# Rev05MergeRedux--LevelShifting_Isolation.net
KiCad netlist of a schematic drawn in Altium Designer
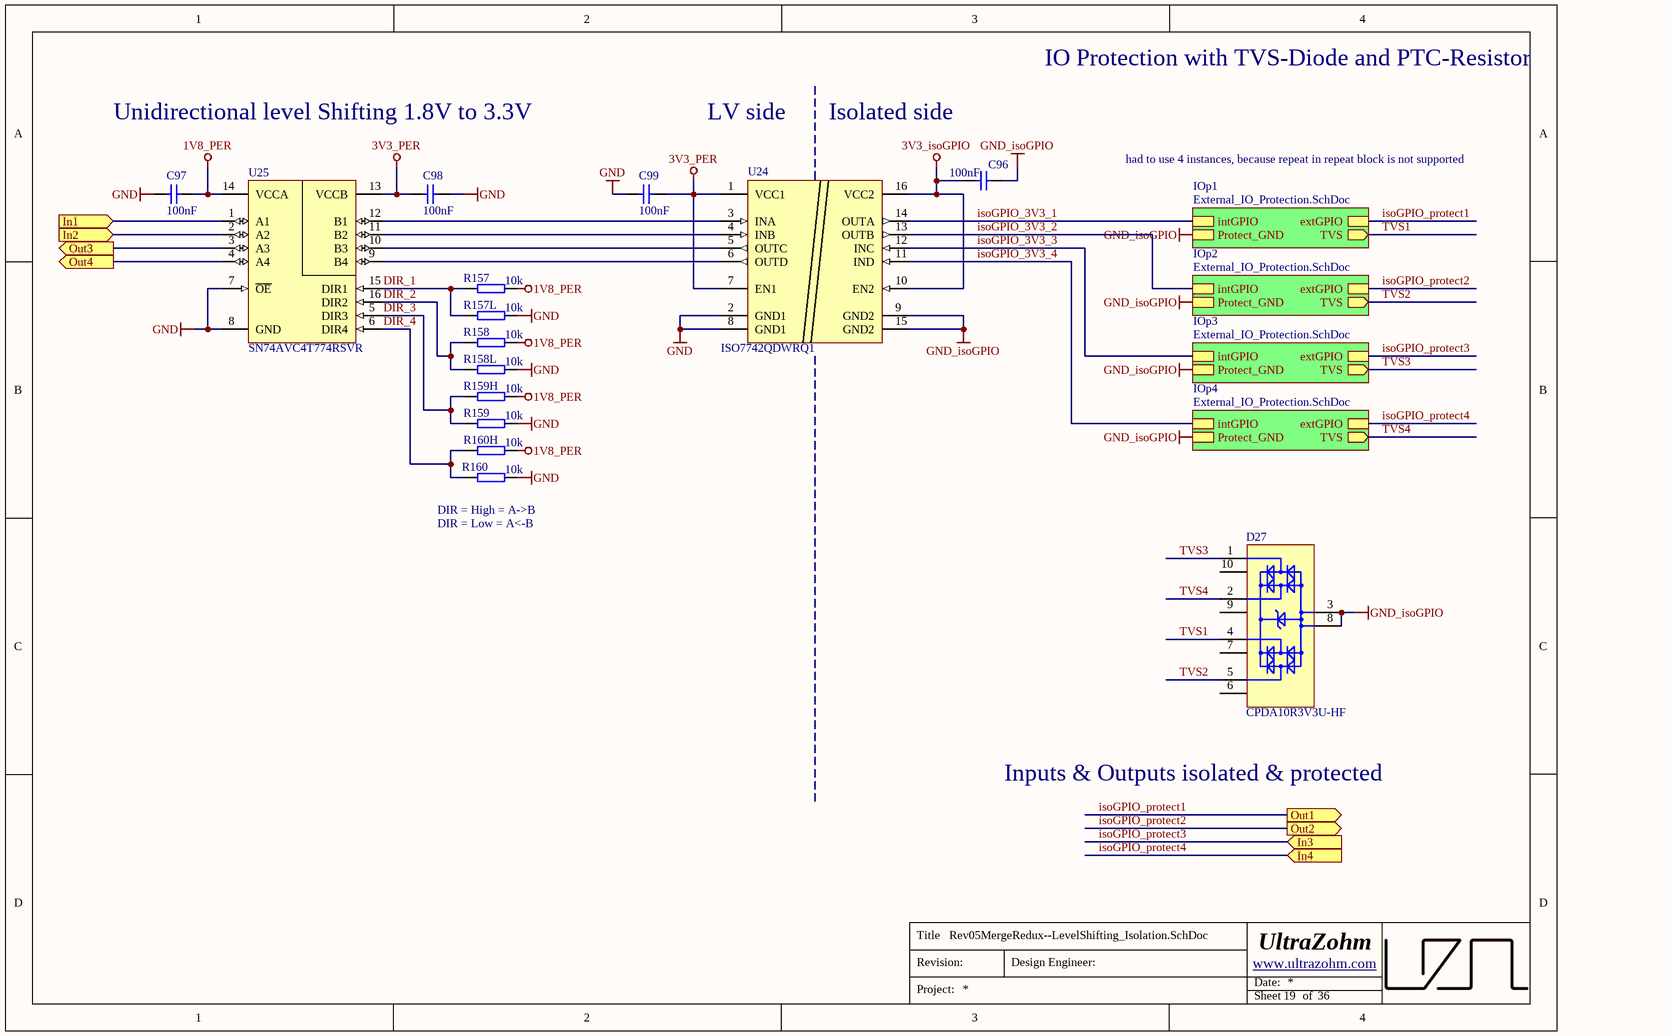
[diagram p0: Rev05MergeRedux--LevelShifting_Isolation.SchDoc]

(export (version "E")
  (design (tool "Eeschema 10.0.6"))
  (components
    (comp (ref "C96")
      (value "100nF")
      (footprint "CAPC1608X90N_V")
      (description "KON 100nF 50V X7R ±10% SMD BF 1608 (0603)")
      (fields (field (name "TOLERANCE") "±10%") (field (name "VOLTAGE") "50V"))
      (libsource (lib "TE") (part "CAP-NP"))
    )
    (comp (ref "C97")
      (value "100nF")
      (footprint "CAPC1608X90N_V")
      (description "KON 100nF 50V X7R ±10% SMD BF 1608 (0603)")
      (fields (field (name "TOLERANCE") "±10%") (field (name "VOLTAGE") "50V"))
      (libsource (lib "TE") (part "CAP-NP"))
    )
    (comp (ref "C98")
      (value "100nF")
      (footprint "CAPC1608X90N_V")
      (description "KON 100nF 50V X7R ±10% SMD BF 1608 (0603)")
      (fields (field (name "TOLERANCE") "±10%") (field (name "VOLTAGE") "50V"))
      (libsource (lib "TE") (part "CAP-NP"))
    )
    (comp (ref "C99")
      (value "100nF")
      (footprint "CAPC1608X90N_V")
      (description "KON 100nF 50V X7R ±10% SMD BF 1608 (0603)")
      (fields (field (name "TOLERANCE") "±10%") (field (name "VOLTAGE") "50V"))
      (libsource (lib "TE") (part "CAP-NP"))
    )
    (comp (ref "D27")
      (value "CPDA10R3V3U-HF")
      (footprint "DFN230X100X55X10N")
      (fields (field (name "VOLTAGE") "3.3V"))
      (libsource (lib "TE") (part "DIODE_ARR_10N_1"))
    )
    (comp (ref "R157")
      (value "10k")
      (footprint "R_0603_TE")
      (description "Generic resistor")
      (fields
        (field (name "TOLERANCE") "1 %")
        (field (name "MANUFACTURER PART NUMBER") "UZgen_R_0603_10k")
        (field (name "CREATED FROM") "AGeiger")
      )
      (libsource (lib "user") (part "RES"))
    )
    (comp (ref "R157L")
      (value "10k")
      (footprint "R_0603_TE")
      (description "Generic resistor")
      (fields
        (field (name "TOLERANCE") "1 %")
        (field (name "MANUFACTURER PART NUMBER") "UZgen_R_0603_10k")
        (field (name "CREATED FROM") "AGeiger")
      )
      (libsource (lib "user") (part "RES"))
    )
    (comp (ref "R158")
      (value "10k")
      (footprint "R_0603_TE")
      (description "Generic resistor")
      (fields
        (field (name "TOLERANCE") "1 %")
        (field (name "MANUFACTURER PART NUMBER") "UZgen_R_0603_10k")
        (field (name "CREATED FROM") "AGeiger")
      )
      (libsource (lib "user") (part "RES"))
    )
    (comp (ref "R158L")
      (value "10k")
      (footprint "R_0603_TE")
      (description "Generic resistor")
      (fields
        (field (name "TOLERANCE") "1 %")
        (field (name "MANUFACTURER PART NUMBER") "UZgen_R_0603_10k")
        (field (name "CREATED FROM") "AGeiger")
      )
      (libsource (lib "user") (part "RES"))
    )
    (comp (ref "R159")
      (value "10k")
      (footprint "R_0603_TE")
      (description "Generic resistor")
      (fields
        (field (name "TOLERANCE") "1 %")
        (field (name "MANUFACTURER PART NUMBER") "UZgen_R_0603_10k")
        (field (name "CREATED FROM") "AGeiger")
      )
      (libsource (lib "user") (part "RES"))
    )
    (comp (ref "R159H")
      (value "10k")
      (footprint "R_0603_TE")
      (description "Generic resistor")
      (fields
        (field (name "TOLERANCE") "1 %")
        (field (name "MANUFACTURER PART NUMBER") "UZgen_R_0603_10k")
        (field (name "CREATED FROM") "AGeiger")
      )
      (libsource (lib "user") (part "RES"))
    )
    (comp (ref "R160")
      (value "10k")
      (footprint "R_0603_TE")
      (description "Generic resistor")
      (fields
        (field (name "TOLERANCE") "1 %")
        (field (name "MANUFACTURER PART NUMBER") "UZgen_R_0603_10k")
        (field (name "CREATED FROM") "AGeiger")
      )
      (libsource (lib "user") (part "RES"))
    )
    (comp (ref "R160H")
      (value "10k")
      (footprint "R_0603_TE")
      (description "Generic resistor")
      (fields
        (field (name "TOLERANCE") "1 %")
        (field (name "MANUFACTURER PART NUMBER") "UZgen_R_0603_10k")
        (field (name "CREATED FROM") "AGeiger")
      )
      (libsource (lib "user") (part "RES"))
    )
    (comp (ref "U24")
      (value "ISO7742QDWRQ1")
      (footprint "SOIC127P1030X265-16N")
      (libsource (lib "TE") (part "ISO7742"))
    )
    (comp (ref "U25")
      (value "SN74AVC4T774RSVR")
      (footprint "QFN40P260X180X55-16N")
      (libsource (lib "TE") (part "SN74AVC4T774RSVR"))
    )
  )
  (nets
    (net (code "2") (name "/DIR_1") (class "Default")
      (node (ref "R157") (pin "1") (pinfunction "1_1") (pintype "passive"))
      (node (ref "R157L") (pin "1") (pinfunction "1_1") (pintype "passive"))
      (node (ref "U25") (pin "15") (pinfunction "DIR1_15") (pintype "input"))
    )
    (net (code "3") (name "/DIR_2") (class "Default")
      (node (ref "R158") (pin "1") (pinfunction "1_1") (pintype "passive"))
      (node (ref "R158L") (pin "1") (pinfunction "1_1") (pintype "passive"))
      (node (ref "U25") (pin "16") (pinfunction "DIR2_16") (pintype "input"))
    )
    (net (code "4") (name "/DIR_3") (class "Default")
      (node (ref "R159") (pin "1") (pinfunction "1_1") (pintype "passive"))
      (node (ref "R159H") (pin "1") (pinfunction "1_1") (pintype "passive"))
      (node (ref "U25") (pin "5") (pinfunction "DIR3_5") (pintype "input"))
    )
    (net (code "5") (name "/DIR_4") (class "Default")
      (node (ref "R160") (pin "1") (pinfunction "1_1") (pintype "passive"))
      (node (ref "R160H") (pin "1") (pinfunction "1_1") (pintype "passive"))
      (node (ref "U25") (pin "6") (pinfunction "DIR4_6") (pintype "input"))
    )
    (net (code "6") (name "/In1") (class "Default")
      (node (ref "U25") (pin "1") (pinfunction "A1_1") (pintype "bidirectional"))
    )
    (net (code "7") (name "/In2") (class "Default")
      (node (ref "U25") (pin "2") (pinfunction "A2_2") (pintype "bidirectional"))
    )
    (net (code "8") (name "/Out3") (class "Default")
      (node (ref "U25") (pin "3") (pinfunction "A3_3") (pintype "bidirectional"))
    )
    (net (code "9") (name "/Out4") (class "Default")
      (node (ref "U25") (pin "4") (pinfunction "A4_4") (pintype "bidirectional"))
    )
    (net (code "10") (name "/TVS1") (class "Default")
      (node (ref "D27") (pin "4") (pinfunction "4_4") (pintype "passive"))
    )
    (net (code "11") (name "/TVS2") (class "Default")
      (node (ref "D27") (pin "5") (pinfunction "5_5") (pintype "passive"))
    )
    (net (code "12") (name "/TVS3") (class "Default")
      (node (ref "D27") (pin "1") (pinfunction "1_1") (pintype "passive"))
    )
    (net (code "13") (name "/TVS4") (class "Default")
      (node (ref "D27") (pin "2") (pinfunction "2_2") (pintype "passive"))
    )
    (net (code "14") (name "/isoGPIO_3V3_1") (class "Default")
      (node (ref "U24") (pin "14") (pinfunction "OUTA_14") (pintype "output"))
    )
    (net (code "15") (name "/isoGPIO_3V3_2") (class "Default")
      (node (ref "U24") (pin "13") (pinfunction "OUTB_13") (pintype "output"))
    )
    (net (code "16") (name "/isoGPIO_3V3_3") (class "Default")
      (node (ref "U24") (pin "12") (pinfunction "INC_12") (pintype "input"))
    )
    (net (code "17") (name "/isoGPIO_3V3_4") (class "Default")
      (node (ref "U24") (pin "11") (pinfunction "IND_11") (pintype "input"))
    )
    (net (code "22") (name "1V8_PER") (class "Default")
      (node (ref "C97") (pin "1") (pinfunction "1_1") (pintype "passive"))
      (node (ref "R157") (pin "2") (pinfunction "2_2") (pintype "passive"))
      (node (ref "R158") (pin "2") (pinfunction "2_2") (pintype "passive"))
      (node (ref "R159H") (pin "2") (pinfunction "2_2") (pintype "passive"))
      (node (ref "R160H") (pin "2") (pinfunction "2_2") (pintype "passive"))
      (node (ref "U25") (pin "14") (pinfunction "VCCA_14") (pintype "power_in"))
    )
    (net (code "23") (name "3V3_PER") (class "Default")
      (node (ref "C98") (pin "2") (pinfunction "2_2") (pintype "passive"))
      (node (ref "C99") (pin "2") (pinfunction "2_2") (pintype "passive"))
      (node (ref "U24") (pin "1") (pinfunction "VCC1_1") (pintype "power_in"))
      (node (ref "U24") (pin "7") (pinfunction "EN1_7") (pintype "passive"))
      (node (ref "U25") (pin "13") (pinfunction "VCCB_13") (pintype "power_in"))
    )
    (net (code "24") (name "3V3_isoGPIO") (class "Default")
      (node (ref "C96") (pin "1") (pinfunction "1_1") (pintype "passive"))
      (node (ref "U24") (pin "10") (pinfunction "EN2_10") (pintype "input"))
      (node (ref "U24") (pin "16") (pinfunction "VCC2_16") (pintype "power_in"))
    )
    (net (code "25") (name "GND") (class "Default")
      (node (ref "C97") (pin "2") (pinfunction "2_2") (pintype "passive"))
      (node (ref "C98") (pin "1") (pinfunction "1_1") (pintype "passive"))
      (node (ref "C99") (pin "1") (pinfunction "1_1") (pintype "passive"))
      (node (ref "R157L") (pin "2") (pinfunction "2_2") (pintype "passive"))
      (node (ref "R158L") (pin "2") (pinfunction "2_2") (pintype "passive"))
      (node (ref "R159") (pin "2") (pinfunction "2_2") (pintype "passive"))
      (node (ref "R160") (pin "2") (pinfunction "2_2") (pintype "passive"))
      (node (ref "U24") (pin "2") (pinfunction "GND1_2") (pintype "power_in"))
      (node (ref "U24") (pin "8") (pinfunction "GND1_8") (pintype "power_in"))
      (node (ref "U25") (pin "7") (pinfunction "~{OE}_7") (pintype "input"))
      (node (ref "U25") (pin "8") (pinfunction "GND_8") (pintype "power_in"))
    )
    (net (code "26") (name "GND_isoGPIO") (class "Default")
      (node (ref "C96") (pin "2") (pinfunction "2_2") (pintype "passive"))
      (node (ref "D27") (pin "3") (pinfunction "3_3") (pintype "passive"))
      (node (ref "D27") (pin "8") (pinfunction "8_8") (pintype "passive"))
      (node (ref "U24") (pin "15") (pinfunction "GND2_15") (pintype "power_in"))
      (node (ref "U24") (pin "9") (pinfunction "GND2_9") (pintype "power_in"))
    )
    (net (code "27") (name "Net-(U24-INA)") (class "Default")
      (node (ref "U24") (pin "3") (pinfunction "INA_3") (pintype "input"))
      (node (ref "U25") (pin "12") (pinfunction "B1_12") (pintype "bidirectional"))
    )
    (net (code "28") (name "Net-(U24-INB)") (class "Default")
      (node (ref "U24") (pin "4") (pinfunction "INB_4") (pintype "input"))
      (node (ref "U25") (pin "11") (pinfunction "B2_11") (pintype "bidirectional"))
    )
    (net (code "29") (name "Net-(U24-OUTC)") (class "Default")
      (node (ref "U24") (pin "5") (pinfunction "OUTC_5") (pintype "output"))
      (node (ref "U25") (pin "10") (pinfunction "B3_10") (pintype "bidirectional"))
    )
    (net (code "30") (name "Net-(U24-OUTD)") (class "Default")
      (node (ref "U24") (pin "6") (pinfunction "OUTD_6") (pintype "output"))
      (node (ref "U25") (pin "9") (pinfunction "B4_9") (pintype "bidirectional"))
    )
    (net (code "31") (name "unconnected-(D27-Pad6)") (class "Default")
      (node (ref "D27") (pin "6") (pinfunction "6_6") (pintype "passive"))
    )
    (net (code "32") (name "unconnected-(D27-Pad7)") (class "Default")
      (node (ref "D27") (pin "7") (pinfunction "7_7") (pintype "passive"))
    )
    (net (code "33") (name "unconnected-(D27-Pad9)") (class "Default")
      (node (ref "D27") (pin "9") (pinfunction "9_9") (pintype "passive"))
    )
    (net (code "34") (name "unconnected-(D27-Pad10)") (class "Default")
      (node (ref "D27") (pin "10") (pinfunction "10_10") (pintype "passive"))
    )
  )
)
